# MCU.net
KiCad netlist of a schematic drawn in Altium Designer
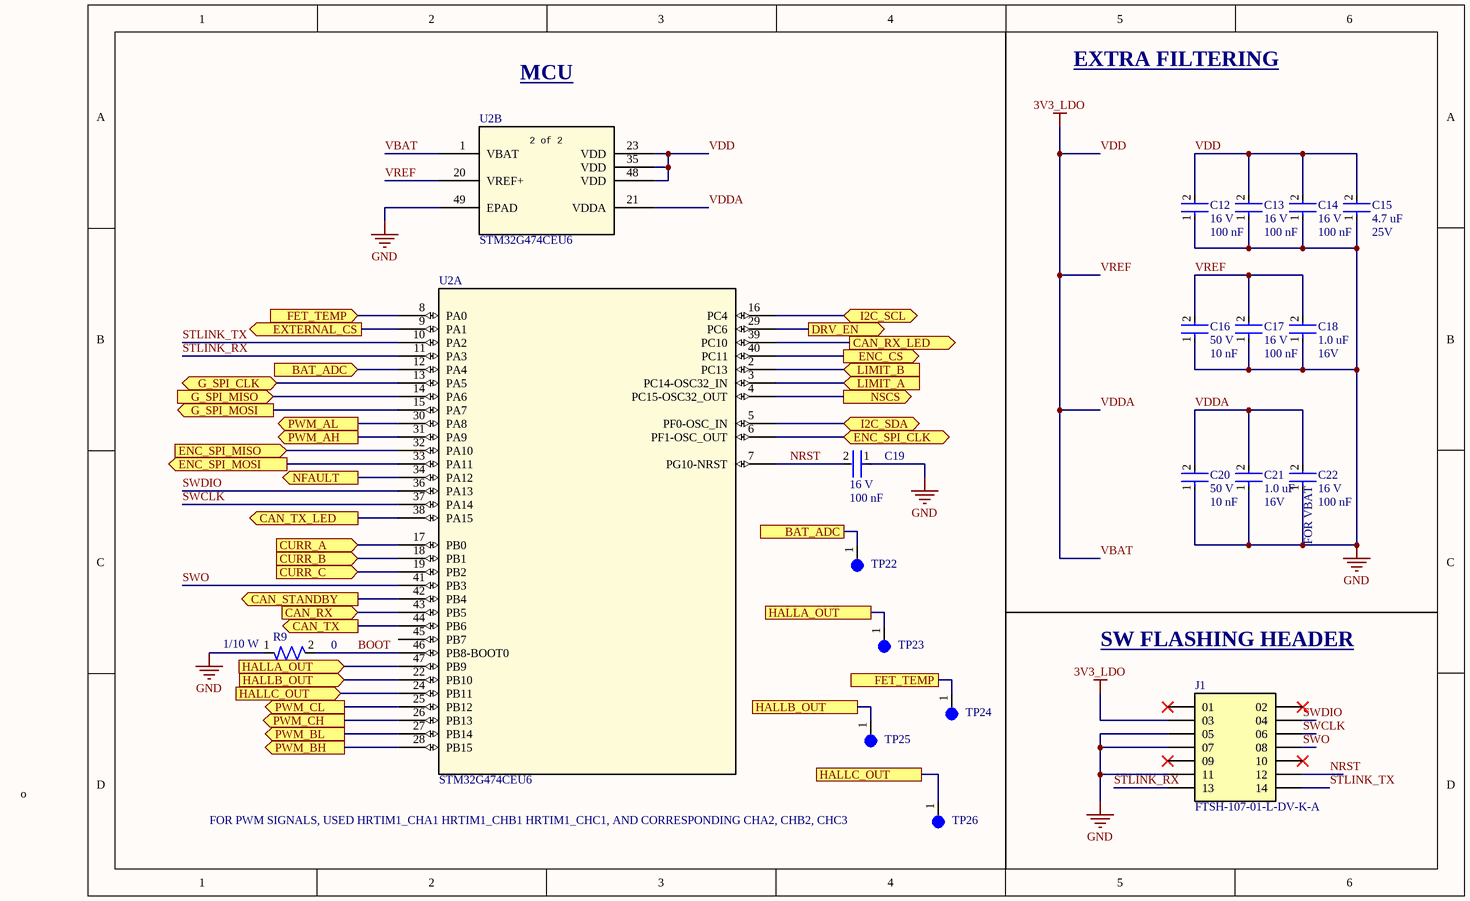
[diagram p0: MCU.SchDoc]

(export (version "E")
  (design (tool "Eeschema 10.0.6"))
  (components
    (comp (ref "C12")
      (value "CC0402KRX7R7BB104")
      (footprint "CAP-0402")
      (description "CAP CER 0.1UF 16V X7R 0402")
      (fields (field (name "VOLTAGE RATING") "16 V") (field (name "CAPACITANCE") "100 nF"))
      (libsource (lib "JLC_25") (part "CAP-0.1U-0001"))
    )
    (comp (ref "C13")
      (value "CC0402KRX7R7BB104")
      (footprint "CAP-0402")
      (description "CAP CER 0.1UF 16V X7R 0402")
      (fields (field (name "VOLTAGE RATING") "16 V") (field (name "CAPACITANCE") "100 nF"))
      (libsource (lib "JLC_25") (part "CAP-0.1U-0001"))
    )
    (comp (ref "C14")
      (value "CC0402KRX7R7BB104")
      (footprint "CAP-0402")
      (description "CAP CER 0.1UF 16V X7R 0402")
      (fields (field (name "VOLTAGE RATING") "16 V") (field (name "CAPACITANCE") "100 nF"))
      (libsource (lib "JLC_25") (part "CAP-0.1U-0001"))
    )
    (comp (ref "C15")
      (value "CC0603KRX5R8BB475")
      (footprint "CAP-0603")
      (description "CAP CER 4.7UF 25V X5R 0603")
      (fields (field (name "CAPACITANCE") "4.7 uF") (field (name "VOLTAGE") "25V"))
      (libsource (lib "JLC_25") (part "CAP-4.7U-0001"))
    )
    (comp (ref "C16")
      (value "CC0603KPX7R9BB103")
      (footprint "CAP-0603")
      (description "CAP CER 10000PF 50V X7R 0603")
      (fields (field (name "VOLTAGE") "50 V") (field (name "CAPACITANCE") "10 nF"))
      (libsource (lib "JLC_25") (part "CAP-10N-0002"))
    )
    (comp (ref "C17")
      (value "CC0402KRX7R7BB104")
      (footprint "CAP-0402")
      (description "CAP CER 0.1UF 16V X7R 0402")
      (fields (field (name "VOLTAGE RATING") "16 V") (field (name "CAPACITANCE") "100 nF"))
      (libsource (lib "JLC_25") (part "CAP-0.1U-0001"))
    )
    (comp (ref "C18")
      (value "CC0603KRX7R7BB105")
      (footprint "CAP-0603")
      (description "CAP CER 1UF 16V X7R 0603")
      (fields (field (name "CAPACITANCE") "1.0 uF") (field (name "VOLTAGE") "16V"))
      (libsource (lib "JLC_25") (part "CAP-1U-0002"))
    )
    (comp (ref "C19")
      (value "CC0402KRX7R7BB104")
      (footprint "CAP-0402")
      (description "CAP CER 0.1UF 16V X7R 0402")
      (fields (field (name "VOLTAGE RATING") "16 V") (field (name "CAPACITANCE") "100 nF"))
      (libsource (lib "JLC_25") (part "CAP-0.1U-0001"))
    )
    (comp (ref "C20")
      (value "CC0603KPX7R9BB103")
      (footprint "CAP-0603")
      (description "CAP CER 10000PF 50V X7R 0603")
      (fields (field (name "VOLTAGE") "50 V") (field (name "CAPACITANCE") "10 nF"))
      (libsource (lib "JLC_25") (part "CAP-10N-0002"))
    )
    (comp (ref "C21")
      (value "CC0603KRX7R7BB105")
      (footprint "CAP-0603")
      (description "CAP CER 1UF 16V X7R 0603")
      (fields (field (name "CAPACITANCE") "1.0 uF") (field (name "VOLTAGE") "16V"))
      (libsource (lib "JLC_25") (part "CAP-1U-0002"))
    )
    (comp (ref "C22")
      (value "CC0402KRX7R7BB104")
      (footprint "CAP-0402")
      (description "CAP CER 0.1UF 16V X7R 0402")
      (fields (field (name "VOLTAGE RATING") "16 V") (field (name "CAPACITANCE") "100 nF"))
      (libsource (lib "JLC_25") (part "CAP-0.1U-0001"))
    )
    (comp (ref "J1")
      (value "FTSH-107-01-L-DV-K-A")
      (footprint "SAMTEC_FTSH-107-01-L-DV-K")
      (description "Connector Header Surface Mount 14 position 0.050 (1.27mm)")
      (fields (field (name "MF") "Samtec Inc."))
      (libsource (lib "MasterLib") (part "CONN-Flashing"))
    )
    (comp (ref "R9")
      (value "RMCF0603ZT0R00")
      (footprint "RES-0603")
      (description "0 Ohms Jumper 0.1W, 1/10W Chip Resistor 0603 (1608 Metric) Automotive AEC-Q200 Thick Film")
      (fields (field (name "RESISTANCE") "0") (field (name "POWER") "1/10 W"))
      (libsource (lib "MasterLib") (part "RES-0-0001"))
    )
    (comp (ref "TP22")
      (value "5003")
      (footprint "TEST-POINT-0001")
      (description "Oranange PC Test Point, Miniature Phoisphor Bronze Silver Plating Through Hole Mounting Type")
      (libsource (lib "JLC_25") (part "TEST-POINT-0001"))
    )
    (comp (ref "TP23")
      (value "5003")
      (footprint "TEST-POINT-0001")
      (description "Oranange PC Test Point, Miniature Phoisphor Bronze Silver Plating Through Hole Mounting Type")
      (libsource (lib "JLC_25") (part "TEST-POINT-0001"))
    )
    (comp (ref "TP24")
      (value "5003")
      (footprint "TEST-POINT-0001")
      (description "Oranange PC Test Point, Miniature Phoisphor Bronze Silver Plating Through Hole Mounting Type")
      (libsource (lib "JLC_25") (part "TEST-POINT-0001"))
    )
    (comp (ref "TP25")
      (value "5003")
      (footprint "TEST-POINT-0001")
      (description "Oranange PC Test Point, Miniature Phoisphor Bronze Silver Plating Through Hole Mounting Type")
      (libsource (lib "JLC_25") (part "TEST-POINT-0001"))
    )
    (comp (ref "TP26")
      (value "5003")
      (footprint "TEST-POINT-0001")
      (description "Oranange PC Test Point, Miniature Phoisphor Bronze Silver Plating Through Hole Mounting Type")
      (libsource (lib "JLC_25") (part "TEST-POINT-0001"))
    )
    (comp (ref "U2")
      (value "STM32G474CEU6")
      (footprint "IC-QFPN48")
      (description "ARM® Cortex®-M4F STM32G4 Microcontroller IC 32-Bit 170MHz 512KB (512K x 8) FLASH 48-UFQFPN (7x7)")
      (fields (field (name "COPYRIGHT") "Copyright (C) 2025 Ultra Librarian. All rights reserved."))
      (libsource (lib "MasterLib") (part "IC-STM32G474"))
    )
  )
  (nets
    (net (code "1") (name "/BAT_ADC") (class "Default")
      (node (ref "TP22") (pin "1") (pinfunction "0_1") (pintype "passive"))
      (node (ref "U2") (pin "12") (pinfunction "PA4_12") (pintype "bidirectional"))
    )
    (net (code "2") (name "/BOOT") (class "Default")
      (node (ref "R9") (pin "2") (pinfunction "2_2") (pintype "passive"))
      (node (ref "U2") (pin "46") (pinfunction "PB8-BOOT0_46") (pintype "bidirectional"))
    )
    (net (code "3") (name "/CAN_RX") (class "Default")
      (node (ref "U2") (pin "43") (pinfunction "PB5_43") (pintype "bidirectional"))
    )
    (net (code "4") (name "/CAN_RX_LED") (class "Default")
      (node (ref "U2") (pin "39") (pinfunction "PC10_39") (pintype "bidirectional"))
    )
    (net (code "5") (name "/CAN_STANDBY") (class "Default")
      (node (ref "U2") (pin "42") (pinfunction "PB4_42") (pintype "bidirectional"))
    )
    (net (code "6") (name "/CAN_TX") (class "Default")
      (node (ref "U2") (pin "44") (pinfunction "PB6_44") (pintype "bidirectional"))
    )
    (net (code "7") (name "/CAN_TX_LED") (class "Default")
      (node (ref "U2") (pin "38") (pinfunction "PA15_38") (pintype "bidirectional"))
    )
    (net (code "8") (name "/CURR_A") (class "Default")
      (node (ref "U2") (pin "17") (pinfunction "PB0_17") (pintype "bidirectional"))
    )
    (net (code "9") (name "/CURR_B") (class "Default")
      (node (ref "U2") (pin "18") (pinfunction "PB1_18") (pintype "bidirectional"))
    )
    (net (code "10") (name "/CURR_C") (class "Default")
      (node (ref "U2") (pin "19") (pinfunction "PB2_19") (pintype "bidirectional"))
    )
    (net (code "11") (name "/DRV_EN") (class "Default")
      (node (ref "U2") (pin "29") (pinfunction "PC6_29") (pintype "bidirectional"))
    )
    (net (code "12") (name "/ENC_CS") (class "Default")
      (node (ref "U2") (pin "40") (pinfunction "PC11_40") (pintype "bidirectional"))
    )
    (net (code "13") (name "/ENC_SPI_CLK") (class "Default")
      (node (ref "U2") (pin "6") (pinfunction "PF1-OSC_OUT_6") (pintype "bidirectional"))
    )
    (net (code "14") (name "/ENC_SPI_MISO") (class "Default")
      (node (ref "U2") (pin "32") (pinfunction "PA10_32") (pintype "bidirectional"))
    )
    (net (code "15") (name "/ENC_SPI_MOSI") (class "Default")
      (node (ref "U2") (pin "33") (pinfunction "PA11_33") (pintype "bidirectional"))
    )
    (net (code "16") (name "/EXTERNAL_CS") (class "Default")
      (node (ref "U2") (pin "9") (pinfunction "PA1_9") (pintype "bidirectional"))
    )
    (net (code "17") (name "/FET_TEMP") (class "Default")
      (node (ref "TP24") (pin "1") (pinfunction "0_1") (pintype "passive"))
      (node (ref "U2") (pin "8") (pinfunction "PA0_8") (pintype "bidirectional"))
    )
    (net (code "18") (name "/G_SPI_CLK") (class "Default")
      (node (ref "U2") (pin "13") (pinfunction "PA5_13") (pintype "bidirectional"))
    )
    (net (code "19") (name "/G_SPI_MISO") (class "Default")
      (node (ref "U2") (pin "14") (pinfunction "PA6_14") (pintype "bidirectional"))
    )
    (net (code "20") (name "/G_SPI_MOSI") (class "Default")
      (node (ref "U2") (pin "15") (pinfunction "PA7_15") (pintype "bidirectional"))
    )
    (net (code "21") (name "/HALLA_OUT") (class "Default")
      (node (ref "TP23") (pin "1") (pinfunction "0_1") (pintype "passive"))
      (node (ref "U2") (pin "47") (pinfunction "PB9_47") (pintype "bidirectional"))
    )
    (net (code "22") (name "/HALLB_OUT") (class "Default")
      (node (ref "TP25") (pin "1") (pinfunction "0_1") (pintype "passive"))
      (node (ref "U2") (pin "22") (pinfunction "PB10_22") (pintype "bidirectional"))
    )
    (net (code "23") (name "/HALLC_OUT") (class "Default")
      (node (ref "TP26") (pin "1") (pinfunction "0_1") (pintype "passive"))
      (node (ref "U2") (pin "24") (pinfunction "PB11_24") (pintype "bidirectional"))
    )
    (net (code "24") (name "/I2C_SCL") (class "Default")
      (node (ref "U2") (pin "16") (pinfunction "PC4_16") (pintype "bidirectional"))
    )
    (net (code "25") (name "/I2C_SDA") (class "Default")
      (node (ref "U2") (pin "5") (pinfunction "PF0-OSC_IN_5") (pintype "bidirectional"))
    )
    (net (code "26") (name "/LIMIT_A") (class "Default")
      (node (ref "U2") (pin "3") (pinfunction "PC14-OSC32_IN_3") (pintype "bidirectional"))
    )
    (net (code "27") (name "/LIMIT_B") (class "Default")
      (node (ref "U2") (pin "2") (pinfunction "PC13_2") (pintype "bidirectional"))
    )
    (net (code "28") (name "/NFAULT") (class "Default")
      (node (ref "U2") (pin "34") (pinfunction "PA12_34") (pintype "bidirectional"))
    )
    (net (code "29") (name "/NRST") (class "Default")
      (node (ref "C19") (pin "2") (pinfunction "2_2") (pintype "passive"))
      (node (ref "J1") (pin "12") (pinfunction "12_12") (pintype "passive"))
      (node (ref "U2") (pin "7") (pinfunction "PG10-NRST_7") (pintype "bidirectional"))
    )
    (net (code "30") (name "/NSCS") (class "Default")
      (node (ref "U2") (pin "4") (pinfunction "PC15-OSC32_OUT_4") (pintype "bidirectional"))
    )
    (net (code "31") (name "/PWM_AH") (class "Default")
      (node (ref "U2") (pin "31") (pinfunction "PA9_31") (pintype "bidirectional"))
    )
    (net (code "32") (name "/PWM_AL") (class "Default")
      (node (ref "U2") (pin "30") (pinfunction "PA8_30") (pintype "bidirectional"))
    )
    (net (code "33") (name "/PWM_BH") (class "Default")
      (node (ref "U2") (pin "28") (pinfunction "PB15_28") (pintype "bidirectional"))
    )
    (net (code "34") (name "/PWM_BL") (class "Default")
      (node (ref "U2") (pin "27") (pinfunction "PB14_27") (pintype "bidirectional"))
    )
    (net (code "35") (name "/PWM_CH") (class "Default")
      (node (ref "U2") (pin "26") (pinfunction "PB13_26") (pintype "bidirectional"))
    )
    (net (code "36") (name "/PWM_CL") (class "Default")
      (node (ref "U2") (pin "25") (pinfunction "PB12_25") (pintype "bidirectional"))
    )
    (net (code "37") (name "/STLINK_RX") (class "Default")
      (node (ref "J1") (pin "13") (pinfunction "13_13") (pintype "passive"))
      (node (ref "U2") (pin "11") (pinfunction "PA3_11") (pintype "bidirectional"))
    )
    (net (code "38") (name "/STLINK_TX") (class "Default")
      (node (ref "J1") (pin "14") (pinfunction "14_14") (pintype "passive"))
      (node (ref "U2") (pin "10") (pinfunction "PA2_10") (pintype "bidirectional"))
    )
    (net (code "39") (name "/SWCLK") (class "Default")
      (node (ref "J1") (pin "06") (pinfunction "06_06") (pintype "passive"))
      (node (ref "U2") (pin "37") (pinfunction "PA14_37") (pintype "bidirectional"))
    )
    (net (code "40") (name "/SWDIO") (class "Default")
      (node (ref "J1") (pin "04") (pinfunction "04_04") (pintype "passive"))
      (node (ref "U2") (pin "36") (pinfunction "PA13_36") (pintype "bidirectional"))
    )
    (net (code "41") (name "/SWO") (class "Default")
      (node (ref "J1") (pin "08") (pinfunction "08_08") (pintype "passive"))
      (node (ref "U2") (pin "41") (pinfunction "PB3_41") (pintype "bidirectional"))
    )
    (net (code "42") (name "3V3_LDO") (class "Default")
      (node (ref "C12") (pin "2") (pinfunction "2_2") (pintype "passive"))
      (node (ref "C13") (pin "2") (pinfunction "2_2") (pintype "passive"))
      (node (ref "C14") (pin "2") (pinfunction "2_2") (pintype "passive"))
      (node (ref "C15") (pin "2") (pinfunction "2_2") (pintype "passive"))
      (node (ref "C16") (pin "2") (pinfunction "2_2") (pintype "passive"))
      (node (ref "C17") (pin "2") (pinfunction "2_2") (pintype "passive"))
      (node (ref "C18") (pin "2") (pinfunction "2_2") (pintype "passive"))
      (node (ref "C20") (pin "2") (pinfunction "2_2") (pintype "passive"))
      (node (ref "C21") (pin "2") (pinfunction "2_2") (pintype "passive"))
      (node (ref "C22") (pin "2") (pinfunction "2_2") (pintype "passive"))
      (node (ref "J1") (pin "03") (pinfunction "03_03") (pintype "passive"))
      (node (ref "U2") (pin "1") (pinfunction "VBAT_1") (pintype "power_in"))
      (node (ref "U2") (pin "20") (pinfunction "VREF+_20") (pintype "power_in"))
      (node (ref "U2") (pin "21") (pinfunction "VDDA_21") (pintype "power_in"))
      (node (ref "U2") (pin "23") (pinfunction "VDD_23") (pintype "power_in"))
      (node (ref "U2") (pin "35") (pinfunction "VDD_35") (pintype "power_in"))
      (node (ref "U2") (pin "48") (pinfunction "VDD_48") (pintype "power_in"))
    )
    (net (code "43") (name "GND") (class "Default")
      (node (ref "C12") (pin "1") (pinfunction "1_1") (pintype "passive"))
      (node (ref "C13") (pin "1") (pinfunction "1_1") (pintype "passive"))
      (node (ref "C14") (pin "1") (pinfunction "1_1") (pintype "passive"))
      (node (ref "C15") (pin "1") (pinfunction "1_1") (pintype "passive"))
      (node (ref "C16") (pin "1") (pinfunction "1_1") (pintype "passive"))
      (node (ref "C17") (pin "1") (pinfunction "1_1") (pintype "passive"))
      (node (ref "C18") (pin "1") (pinfunction "1_1") (pintype "passive"))
      (node (ref "C19") (pin "1") (pinfunction "1_1") (pintype "passive"))
      (node (ref "C20") (pin "1") (pinfunction "1_1") (pintype "passive"))
      (node (ref "C21") (pin "1") (pinfunction "1_1") (pintype "passive"))
      (node (ref "C22") (pin "1") (pinfunction "1_1") (pintype "passive"))
      (node (ref "J1") (pin "05") (pinfunction "05_05") (pintype "passive"))
      (node (ref "J1") (pin "07") (pinfunction "07_07") (pintype "passive"))
      (node (ref "J1") (pin "11") (pinfunction "11_11") (pintype "passive"))
      (node (ref "R9") (pin "1") (pinfunction "1_1") (pintype "passive"))
      (node (ref "U2") (pin "49") (pinfunction "EPAD_49") (pintype "passive"))
    )
    (net (code "44") (name "unconnected-(J1-Pad01)") (class "Default")
      (node (ref "J1") (pin "01") (pinfunction "01_01") (pintype "passive+no_connect"))
    )
    (net (code "45") (name "unconnected-(J1-Pad02)") (class "Default")
      (node (ref "J1") (pin "02") (pinfunction "02_02") (pintype "passive+no_connect"))
    )
    (net (code "46") (name "unconnected-(J1-Pad09)") (class "Default")
      (node (ref "J1") (pin "09") (pinfunction "09_09") (pintype "passive+no_connect"))
    )
    (net (code "47") (name "unconnected-(J1-Pad10)") (class "Default")
      (node (ref "J1") (pin "10") (pinfunction "10_10") (pintype "passive+no_connect"))
    )
    (net (code "48") (name "unconnected-(U2A-PB7-Pad45)") (class "Default")
      (node (ref "U2") (pin "45") (pinfunction "PB7_45") (pintype "bidirectional"))
    )
  )
)
